# CC2530.net
KiCad netlist of a schematic drawn in Altium Designer
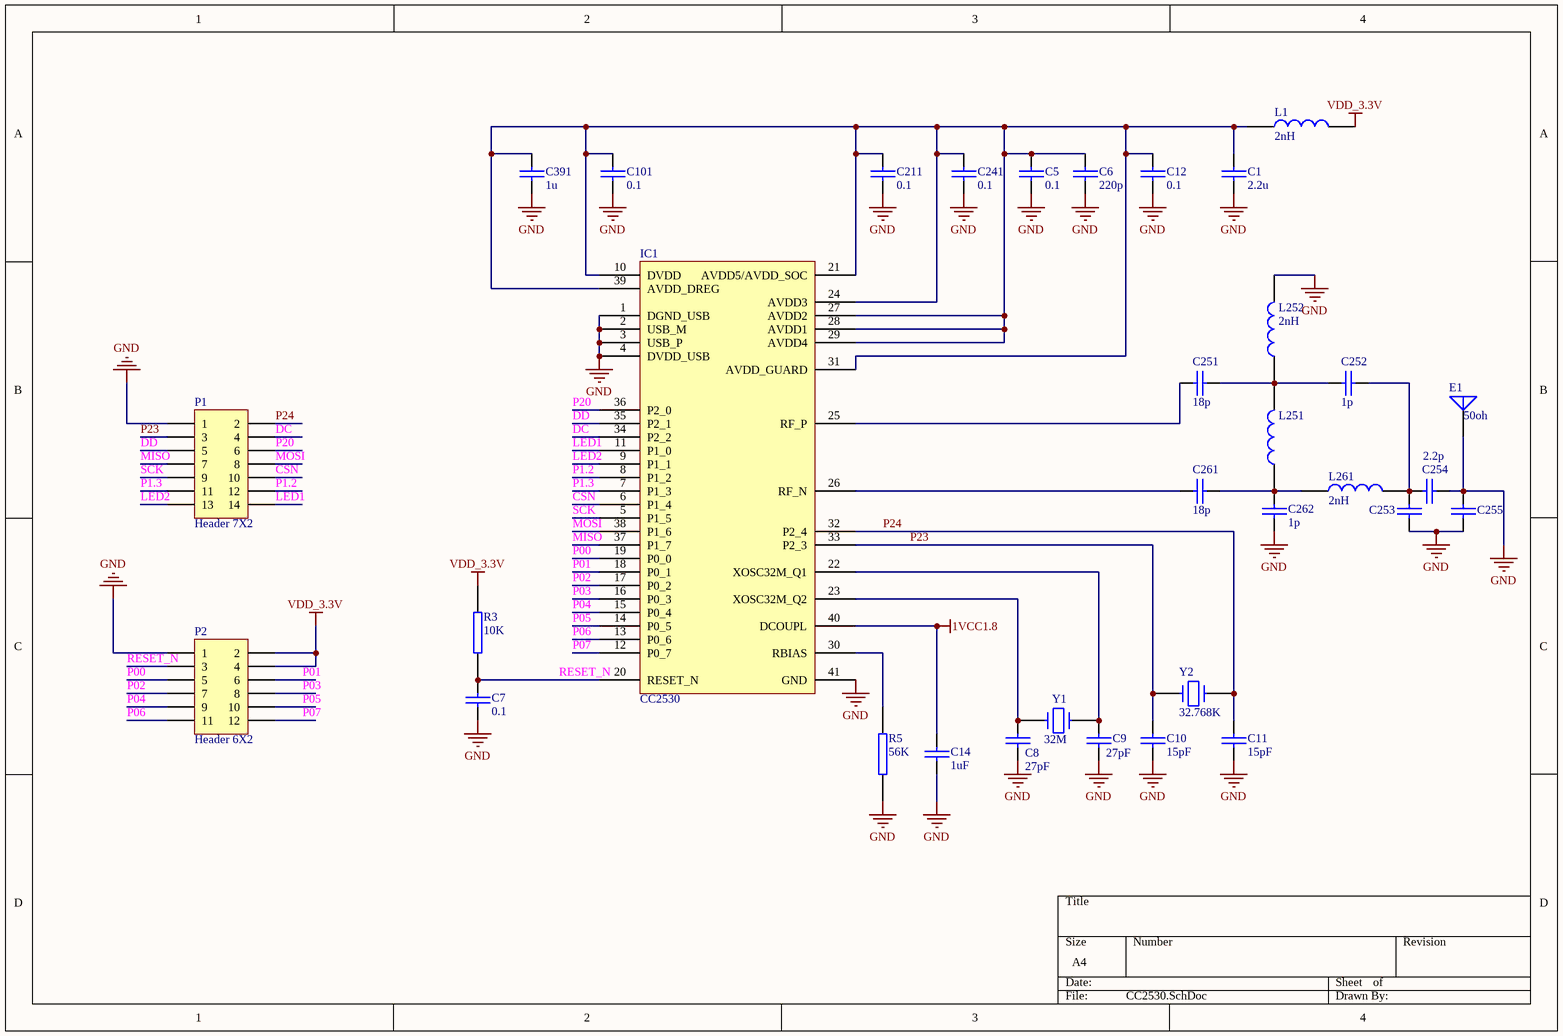
[diagram p0: CC2530.SchDoc]

(export (version "E")
  (design (tool "Eeschema 10.0.6"))
  (components
    (comp (ref "C1")
      (value "2.2u")
      (footprint "0402")
      (description "Capacitor")
      (libsource (lib "Miscellaneous Devices") (part "CAP"))
    )
    (comp (ref "C5")
      (value "0.1")
      (footprint "0402")
      (description "Capacitor")
      (libsource (lib "Miscellaneous Devices") (part "CAP"))
    )
    (comp (ref "C6")
      (value "220p")
      (footprint "0402")
      (description "Capacitor")
      (libsource (lib "Miscellaneous Devices") (part "CAP"))
    )
    (comp (ref "C7")
      (value "0.1")
      (footprint "0402")
      (description "Capacitor")
      (libsource (lib "Miscellaneous Devices") (part "CAP"))
    )
    (comp (ref "C8")
      (value "27pF")
      (footprint "0402")
      (description "Capacitor")
      (libsource (lib "Miscellaneous Devices") (part "CAP"))
    )
    (comp (ref "C9")
      (value "27pF")
      (footprint "0402")
      (description "Capacitor")
      (libsource (lib "Miscellaneous Devices") (part "CAP"))
    )
    (comp (ref "C10")
      (value "15pF")
      (footprint "0402")
      (description "Capacitor")
      (libsource (lib "Miscellaneous Devices") (part "CAP"))
    )
    (comp (ref "C11")
      (value "15pF")
      (footprint "0402")
      (description "Capacitor")
      (libsource (lib "Miscellaneous Devices") (part "CAP"))
    )
    (comp (ref "C12")
      (value "0.1")
      (footprint "0402")
      (description "Capacitor")
      (libsource (lib "Miscellaneous Devices") (part "CAP"))
    )
    (comp (ref "C14")
      (value "1uF")
      (footprint "0402")
      (description "Capacitor")
      (libsource (lib "Miscellaneous Devices") (part "CAP"))
    )
    (comp (ref "C101")
      (value "0.1")
      (footprint "0402")
      (description "Capacitor")
      (libsource (lib "Miscellaneous Devices") (part "CAP"))
    )
    (comp (ref "C211")
      (value "0.1")
      (footprint "0402")
      (description "Capacitor")
      (libsource (lib "Miscellaneous Devices") (part "CAP"))
    )
    (comp (ref "C241")
      (value "0.1")
      (footprint "0402")
      (description "Capacitor")
      (libsource (lib "Miscellaneous Devices") (part "CAP"))
    )
    (comp (ref "C251")
      (value "18p")
      (footprint "0402")
      (description "Capacitor")
      (libsource (lib "Miscellaneous Devices") (part "CAP"))
    )
    (comp (ref "C252")
      (value "1p")
      (footprint "0402")
      (description "Capacitor")
      (libsource (lib "Miscellaneous Devices") (part "CAP"))
    )
    (comp (ref "C253")
      (value "~")
      (footprint "0402")
      (description "Capacitor")
      (libsource (lib "Miscellaneous Devices") (part "CAP"))
    )
    (comp (ref "C254")
      (value "2.2p")
      (footprint "0402")
      (description "Capacitor")
      (libsource (lib "Miscellaneous Devices") (part "CAP"))
    )
    (comp (ref "C255")
      (value "~")
      (footprint "0402")
      (description "Capacitor")
      (libsource (lib "Miscellaneous Devices") (part "CAP"))
    )
    (comp (ref "C261")
      (value "18p")
      (footprint "0402")
      (description "Capacitor")
      (libsource (lib "Miscellaneous Devices") (part "CAP"))
    )
    (comp (ref "C262")
      (value "1p")
      (footprint "0402")
      (description "Capacitor")
      (libsource (lib "Miscellaneous Devices") (part "CAP"))
    )
    (comp (ref "C391")
      (value "1u")
      (footprint "0402")
      (description "Capacitor")
      (libsource (lib "Miscellaneous Devices") (part "CAP"))
    )
    (comp (ref "E1")
      (value "50oh")
      (footprint "ANT")
      (description "Generic Antenna")
      (libsource (lib "Miscellaneous Devices") (part "ANTENNA"))
    )
    (comp (ref "IC1") (value "CC2530") (footprint "PVQFN-N40") (libsource (lib "集成") (part "CC2530")))
    (comp (ref "L1")
      (value "2nH")
      (footprint "0402")
      (libsource (lib "Miscellaneous Devices") (part "INDUCTOR"))
    )
    (comp (ref "L251")
      (value "~")
      (footprint "0402")
      (libsource (lib "Miscellaneous Devices") (part "INDUCTOR"))
    )
    (comp (ref "L252")
      (value "2nH")
      (footprint "0402")
      (libsource (lib "Miscellaneous Devices") (part "INDUCTOR"))
    )
    (comp (ref "L261")
      (value "2nH")
      (footprint "0402")
      (libsource (lib "Miscellaneous Devices") (part "INDUCTOR"))
    )
    (comp (ref "P1")
      (value "Header 7X2")
      (footprint "HDR2X7")
      (description "Header, 7-Pin, Dual row")
      (fields (field (name "PUBLISHER") "Altium Limited"))
      (libsource (lib "Miscellaneous Connectors") (part "Header 7X2"))
    )
    (comp (ref "P2")
      (value "Header 6X2")
      (footprint "HDR2X6")
      (description "Header, 6-Pin, Dual row")
      (fields (field (name "PUBLISHER") "Altium Limited"))
      (libsource (lib "Miscellaneous Connectors") (part "Header 6X2"))
    )
    (comp (ref "R3") (value "10K") (footprint "0402") (libsource (lib "Miscellaneous Devices") (part "RES2")))
    (comp (ref "R5") (value "56K") (footprint "0402") (libsource (lib "Miscellaneous Devices") (part "RES2")))
    (comp (ref "Y1")
      (value "32M")
      (footprint "XT-SMD3225")
      (description "Crystal")
      (libsource (lib "Miscellaneous Devices") (part "CRYSTAL"))
    )
    (comp (ref "Y2")
      (value "32.768K")
      (footprint "XT_3")
      (description "Crystal")
      (libsource (lib "Miscellaneous Devices") (part "CRYSTAL"))
    )
  )
  (nets
    (net (code "1") (name "/CSN") (class "Default")
      (node (ref "IC1") (pin "6") (pinfunction "P1_4_6") (pintype "passive"))
      (node (ref "P1") (pin "10") (pinfunction "10_10") (pintype "passive"))
    )
    (net (code "2") (name "/DC") (class "Default")
      (node (ref "IC1") (pin "34") (pinfunction "P2_2_34") (pintype "passive"))
      (node (ref "P1") (pin "4") (pinfunction "4_4") (pintype "passive"))
    )
    (net (code "3") (name "/DD") (class "Default")
      (node (ref "IC1") (pin "35") (pinfunction "P2_1_35") (pintype "passive"))
      (node (ref "P1") (pin "5") (pinfunction "5_5") (pintype "passive"))
    )
    (net (code "4") (name "/LED1") (class "Default")
      (node (ref "IC1") (pin "11") (pinfunction "P1_0_11") (pintype "passive"))
      (node (ref "P1") (pin "14") (pinfunction "14_14") (pintype "passive"))
    )
    (net (code "5") (name "/LED2") (class "Default")
      (node (ref "IC1") (pin "9") (pinfunction "P1_1_9") (pintype "passive"))
      (node (ref "P1") (pin "13") (pinfunction "13_13") (pintype "passive"))
    )
    (net (code "6") (name "/MISO") (class "Default")
      (node (ref "IC1") (pin "37") (pinfunction "P1_7_37") (pintype "passive"))
      (node (ref "P1") (pin "7") (pinfunction "7_7") (pintype "passive"))
    )
    (net (code "7") (name "/MOSI") (class "Default")
      (node (ref "IC1") (pin "38") (pinfunction "P1_6_38") (pintype "passive"))
      (node (ref "P1") (pin "8") (pinfunction "8_8") (pintype "passive"))
    )
    (net (code "8") (name "/P00") (class "Default")
      (node (ref "IC1") (pin "19") (pinfunction "P0_0_19") (pintype "passive"))
      (node (ref "P2") (pin "5") (pinfunction "5_5") (pintype "passive"))
    )
    (net (code "9") (name "/P01") (class "Default")
      (node (ref "IC1") (pin "18") (pinfunction "P0_1_18") (pintype "passive"))
      (node (ref "P2") (pin "6") (pinfunction "6_6") (pintype "passive"))
    )
    (net (code "10") (name "/P1.2") (class "Default")
      (node (ref "IC1") (pin "8") (pinfunction "P1_2_8") (pintype "passive"))
      (node (ref "P1") (pin "12") (pinfunction "12_12") (pintype "passive"))
    )
    (net (code "11") (name "/P1.3") (class "Default")
      (node (ref "IC1") (pin "7") (pinfunction "P1_3_7") (pintype "passive"))
      (node (ref "P1") (pin "11") (pinfunction "11_11") (pintype "passive"))
    )
    (net (code "12") (name "/P02") (class "Default")
      (node (ref "IC1") (pin "17") (pinfunction "P0_2_17") (pintype "passive"))
      (node (ref "P2") (pin "7") (pinfunction "7_7") (pintype "passive"))
    )
    (net (code "13") (name "/P03") (class "Default")
      (node (ref "IC1") (pin "16") (pinfunction "P0_3_16") (pintype "passive"))
      (node (ref "P2") (pin "8") (pinfunction "8_8") (pintype "passive"))
    )
    (net (code "14") (name "/P04") (class "Default")
      (node (ref "IC1") (pin "15") (pinfunction "P0_4_15") (pintype "passive"))
      (node (ref "P2") (pin "9") (pinfunction "9_9") (pintype "passive"))
    )
    (net (code "15") (name "/P05") (class "Default")
      (node (ref "IC1") (pin "14") (pinfunction "P0_5_14") (pintype "passive"))
      (node (ref "P2") (pin "10") (pinfunction "10_10") (pintype "passive"))
    )
    (net (code "16") (name "/P06") (class "Default")
      (node (ref "IC1") (pin "13") (pinfunction "P0_6_13") (pintype "passive"))
      (node (ref "P2") (pin "11") (pinfunction "11_11") (pintype "passive"))
    )
    (net (code "17") (name "/P07") (class "Default")
      (node (ref "IC1") (pin "12") (pinfunction "P0_7_12") (pintype "passive"))
      (node (ref "P2") (pin "12") (pinfunction "12_12") (pintype "passive"))
    )
    (net (code "18") (name "/P20") (class "Default")
      (node (ref "IC1") (pin "36") (pinfunction "P2_0_36") (pintype "passive"))
      (node (ref "P1") (pin "6") (pinfunction "6_6") (pintype "passive"))
    )
    (net (code "19") (name "/P23") (class "Default")
      (node (ref "C10") (pin "1") (pinfunction "1_1") (pintype "passive"))
      (node (ref "IC1") (pin "33") (pinfunction "P2_3_33") (pintype "passive"))
      (node (ref "P1") (pin "3") (pinfunction "3_3") (pintype "passive"))
      (node (ref "Y2") (pin "2") (pinfunction "2_2") (pintype "passive"))
    )
    (net (code "20") (name "/P24") (class "Default")
      (node (ref "C11") (pin "1") (pinfunction "1_1") (pintype "passive"))
      (node (ref "IC1") (pin "32") (pinfunction "P2_4_32") (pintype "passive"))
      (node (ref "P1") (pin "2") (pinfunction "2_2") (pintype "passive"))
      (node (ref "Y2") (pin "1") (pinfunction "1_1") (pintype "passive"))
    )
    (net (code "21") (name "/RESET_N") (class "Default")
      (node (ref "C7") (pin "1") (pinfunction "1_1") (pintype "passive"))
      (node (ref "IC1") (pin "20") (pinfunction "RESET_N_20") (pintype "passive"))
      (node (ref "P2") (pin "3") (pinfunction "3_3") (pintype "passive"))
      (node (ref "R3") (pin "1") (pinfunction "1_1") (pintype "passive"))
    )
    (net (code "22") (name "/SCK") (class "Default")
      (node (ref "IC1") (pin "5") (pinfunction "P1_5_5") (pintype "passive"))
      (node (ref "P1") (pin "9") (pinfunction "9_9") (pintype "passive"))
    )
    (net (code "23") (name "1VCC1.8") (class "Default")
      (node (ref "C14") (pin "1") (pinfunction "1_1") (pintype "passive"))
      (node (ref "IC1") (pin "40") (pinfunction "DCOUPL_40") (pintype "passive"))
    )
    (net (code "24") (name "GND") (class "Default")
      (node (ref "C1") (pin "2") (pinfunction "2_2") (pintype "passive"))
      (node (ref "C10") (pin "2") (pinfunction "2_2") (pintype "passive"))
      (node (ref "C101") (pin "2") (pinfunction "2_2") (pintype "passive"))
      (node (ref "C11") (pin "2") (pinfunction "2_2") (pintype "passive"))
      (node (ref "C12") (pin "2") (pinfunction "2_2") (pintype "passive"))
      (node (ref "C14") (pin "2") (pinfunction "2_2") (pintype "passive"))
      (node (ref "C211") (pin "2") (pinfunction "2_2") (pintype "passive"))
      (node (ref "C241") (pin "2") (pinfunction "2_2") (pintype "passive"))
      (node (ref "C253") (pin "2") (pinfunction "2_2") (pintype "passive"))
      (node (ref "C254") (pin "2") (pinfunction "2_2") (pintype "passive"))
      (node (ref "C255") (pin "1") (pinfunction "1_1") (pintype "passive"))
      (node (ref "C255") (pin "2") (pinfunction "2_2") (pintype "passive"))
      (node (ref "C262") (pin "2") (pinfunction "2_2") (pintype "passive"))
      (node (ref "C391") (pin "2") (pinfunction "2_2") (pintype "passive"))
      (node (ref "C5") (pin "2") (pinfunction "2_2") (pintype "passive"))
      (node (ref "C6") (pin "2") (pinfunction "2_2") (pintype "passive"))
      (node (ref "C7") (pin "2") (pinfunction "2_2") (pintype "passive"))
      (node (ref "C8") (pin "2") (pinfunction "2_2") (pintype "passive"))
      (node (ref "C9") (pin "2") (pinfunction "2_2") (pintype "passive"))
      (node (ref "E1") (pin "1") (pinfunction "A_1") (pintype "passive"))
      (node (ref "IC1") (pin "1") (pinfunction "DGND_USB_1") (pintype "passive"))
      (node (ref "IC1") (pin "2") (pinfunction "USB_M_2") (pintype "passive"))
      (node (ref "IC1") (pin "3") (pinfunction "USB_P_3") (pintype "passive"))
      (node (ref "IC1") (pin "4") (pinfunction "DVDD_USB_4") (pintype "passive"))
      (node (ref "IC1") (pin "41") (pinfunction "GND_41") (pintype "passive"))
      (node (ref "L252") (pin "2") (pinfunction "2_2") (pintype "passive"))
      (node (ref "P1") (pin "1") (pinfunction "1_1") (pintype "passive"))
      (node (ref "P2") (pin "1") (pinfunction "1_1") (pintype "passive"))
      (node (ref "R5") (pin "2") (pinfunction "2_2") (pintype "passive"))
    )
    (net (code "25") (name "Net-(C251-Pad2)") (class "Default")
      (node (ref "C251") (pin "2") (pinfunction "2_2") (pintype "passive"))
      (node (ref "C252") (pin "1") (pinfunction "1_1") (pintype "passive"))
      (node (ref "L251") (pin "2") (pinfunction "2_2") (pintype "passive"))
      (node (ref "L252") (pin "1") (pinfunction "1_1") (pintype "passive"))
    )
    (net (code "26") (name "Net-(C252-Pad2)") (class "Default")
      (node (ref "C252") (pin "2") (pinfunction "2_2") (pintype "passive"))
      (node (ref "C253") (pin "1") (pinfunction "1_1") (pintype "passive"))
      (node (ref "C254") (pin "1") (pinfunction "1_1") (pintype "passive"))
      (node (ref "L261") (pin "2") (pinfunction "2_2") (pintype "passive"))
    )
    (net (code "27") (name "Net-(C261-Pad2)") (class "Default")
      (node (ref "C261") (pin "2") (pinfunction "2_2") (pintype "passive"))
      (node (ref "C262") (pin "1") (pinfunction "1_1") (pintype "passive"))
      (node (ref "L251") (pin "1") (pinfunction "1_1") (pintype "passive"))
      (node (ref "L261") (pin "1") (pinfunction "1_1") (pintype "passive"))
    )
    (net (code "28") (name "Net-(IC1-AVDD1)") (class "Default")
      (node (ref "C1") (pin "1") (pinfunction "1_1") (pintype "passive"))
      (node (ref "C101") (pin "1") (pinfunction "1_1") (pintype "passive"))
      (node (ref "C12") (pin "1") (pinfunction "1_1") (pintype "passive"))
      (node (ref "C211") (pin "1") (pinfunction "1_1") (pintype "passive"))
      (node (ref "C241") (pin "1") (pinfunction "1_1") (pintype "passive"))
      (node (ref "C391") (pin "1") (pinfunction "1_1") (pintype "passive"))
      (node (ref "C5") (pin "1") (pinfunction "1_1") (pintype "passive"))
      (node (ref "C6") (pin "1") (pinfunction "1_1") (pintype "passive"))
      (node (ref "IC1") (pin "10") (pinfunction "DVDD_10") (pintype "passive"))
      (node (ref "IC1") (pin "21") (pinfunction "AVDD5/AVDD_SOC_21") (pintype "passive"))
      (node (ref "IC1") (pin "24") (pinfunction "AVDD3_24") (pintype "passive"))
      (node (ref "IC1") (pin "27") (pinfunction "AVDD2_27") (pintype "passive"))
      (node (ref "IC1") (pin "28") (pinfunction "AVDD1_28") (pintype "passive"))
      (node (ref "IC1") (pin "29") (pinfunction "AVDD4_29") (pintype "passive"))
      (node (ref "IC1") (pin "31") (pinfunction "AVDD_GUARD_31") (pintype "passive"))
      (node (ref "IC1") (pin "39") (pinfunction "AVDD_DREG_39") (pintype "passive"))
      (node (ref "L1") (pin "1") (pinfunction "1_1") (pintype "passive"))
    )
    (net (code "29") (name "Net-(IC1-RBIAS)") (class "Default")
      (node (ref "IC1") (pin "30") (pinfunction "RBIAS_30") (pintype "passive"))
      (node (ref "R5") (pin "1") (pinfunction "1_1") (pintype "passive"))
    )
    (net (code "30") (name "Net-(IC1-RF_N)") (class "Default")
      (node (ref "C261") (pin "1") (pinfunction "1_1") (pintype "passive"))
      (node (ref "IC1") (pin "26") (pinfunction "RF_N_26") (pintype "passive"))
    )
    (net (code "31") (name "Net-(IC1-RF_P)") (class "Default")
      (node (ref "C251") (pin "1") (pinfunction "1_1") (pintype "passive"))
      (node (ref "IC1") (pin "25") (pinfunction "RF_P_25") (pintype "passive"))
    )
    (net (code "32") (name "Net-(IC1-XOSC32M_Q1)") (class "Default")
      (node (ref "C9") (pin "1") (pinfunction "1_1") (pintype "passive"))
      (node (ref "IC1") (pin "22") (pinfunction "XOSC32M_Q1_22") (pintype "passive"))
      (node (ref "Y1") (pin "2") (pinfunction "2_2") (pintype "passive"))
    )
    (net (code "33") (name "Net-(IC1-XOSC32M_Q2)") (class "Default")
      (node (ref "C8") (pin "1") (pinfunction "1_1") (pintype "passive"))
      (node (ref "IC1") (pin "23") (pinfunction "XOSC32M_Q2_23") (pintype "passive"))
      (node (ref "Y1") (pin "1") (pinfunction "1_1") (pintype "passive"))
    )
    (net (code "34") (name "VDD_3.3V") (class "Default")
      (node (ref "L1") (pin "2") (pinfunction "2_2") (pintype "passive"))
      (node (ref "P2") (pin "2") (pinfunction "2_2") (pintype "passive"))
      (node (ref "P2") (pin "4") (pinfunction "4_4") (pintype "passive"))
      (node (ref "R3") (pin "2") (pinfunction "2_2") (pintype "passive"))
    )
  )
)
